# BootDriver.net
KiCad netlist of a schematic drawn in Altium Designer
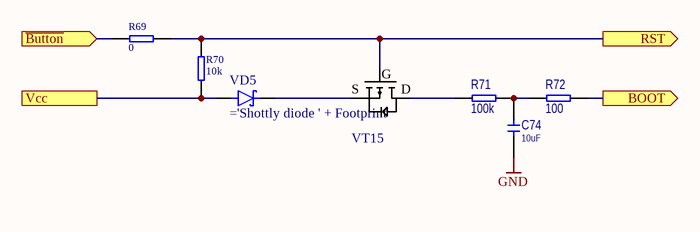
[diagram p0: BootDriver.SchDoc]

(export (version "E")
  (design (tool "Eeschema 10.0.6"))
  (components
    (comp (ref "C74")
      (value "10uF")
      (footprint "CERCAP 0603")
      (description "Capacitor")
      (fields (field (name "VOLTAGE") "50V") (field (name "Comment") "CERCAP 0603 10uF 50V X7R"))
      (libsource (lib "!main") (part "!Capacitor"))
    )
    (comp (ref "R69")
      (value "0")
      (footprint "RES 0402")
      (description "Resistor")
      (fields (field (name "Comment") "RES 0402 0"))
      (libsource (lib "!main") (part "!Resistor"))
    )
    (comp (ref "R70")
      (value "10k")
      (footprint "RES 0402")
      (description "Resistor")
      (fields (field (name "Comment") "RES 0402 10k"))
      (libsource (lib "!main") (part "!Resistor"))
    )
    (comp (ref "R71")
      (value "100k")
      (footprint "RES 0402")
      (description "Resistor")
      (fields (field (name "Comment") "RES 0402 100k"))
      (libsource (lib "!main") (part "!Resistor"))
    )
    (comp (ref "R72")
      (value "100")
      (footprint "RES 0402")
      (description "Resistor")
      (fields (field (name "Comment") "RES 0402 100"))
      (libsource (lib "!main") (part "!Resistor"))
    )
    (comp (ref "VD5")
      (value "Shottly diode SOD-123")
      (footprint "SOD-123")
      (description "Diode Shottky")
      (libsource (lib "diodes") (part "DiodeS"))
    )
    (comp (ref "VT15")
      (value "AO3407A")
      (footprint "SOT23-3")
      (description "generic P mosfet")
      (libsource (lib "transistors") (part "!Generic P MOSFET"))
    )
  )
  (nets
    (net (code "1") (name "/BOOT") (class "Default")
      (node (ref "R72") (pin "2") (pinfunction "12_2") (pintype "passive"))
    )
    (net (code "2") (name "/RST") (class "Default")
      (node (ref "R69") (pin "2") (pinfunction "12_2") (pintype "passive"))
      (node (ref "R70") (pin "2") (pinfunction "12_2") (pintype "passive"))
      (node (ref "VT15") (pin "G2") (pintype "passive"))
    )
    (net (code "3") (name "/Vcc") (class "Default")
      (node (ref "R70") (pin "1") (pinfunction "11_1") (pintype "passive"))
      (node (ref "VD5") (pin "A") (pinfunction "Anode_A") (pintype "passive"))
    )
    (net (code "4") (name "/~{Button}") (class "Default")
      (node (ref "R69") (pin "1") (pinfunction "11_1") (pintype "passive"))
    )
    (net (code "5") (name "GND") (class "Default") (node (ref "C74") (pin "1") (pintype "passive")))
    (net (code "6") (name "Net-(R71-11)") (class "Default")
      (node (ref "R71") (pin "1") (pinfunction "11_1") (pintype "passive"))
      (node (ref "VT15") (pin "D1") (pintype "passive"))
    )
    (net (code "7") (name "Net-(R71-12)") (class "Default")
      (node (ref "C74") (pin "2") (pintype "passive"))
      (node (ref "R71") (pin "2") (pinfunction "12_2") (pintype "passive"))
      (node (ref "R72") (pin "1") (pinfunction "11_1") (pintype "passive"))
    )
    (net (code "8") (name "Net-(VD5-Cathode)") (class "Default")
      (node (ref "VD5") (pin "C") (pinfunction "Cathode_C") (pintype "passive"))
      (node (ref "VT15") (pin "S1") (pintype "passive"))
    )
  )
)
